# LEDMaster.net
KiCad netlist of a schematic drawn in EAGLE
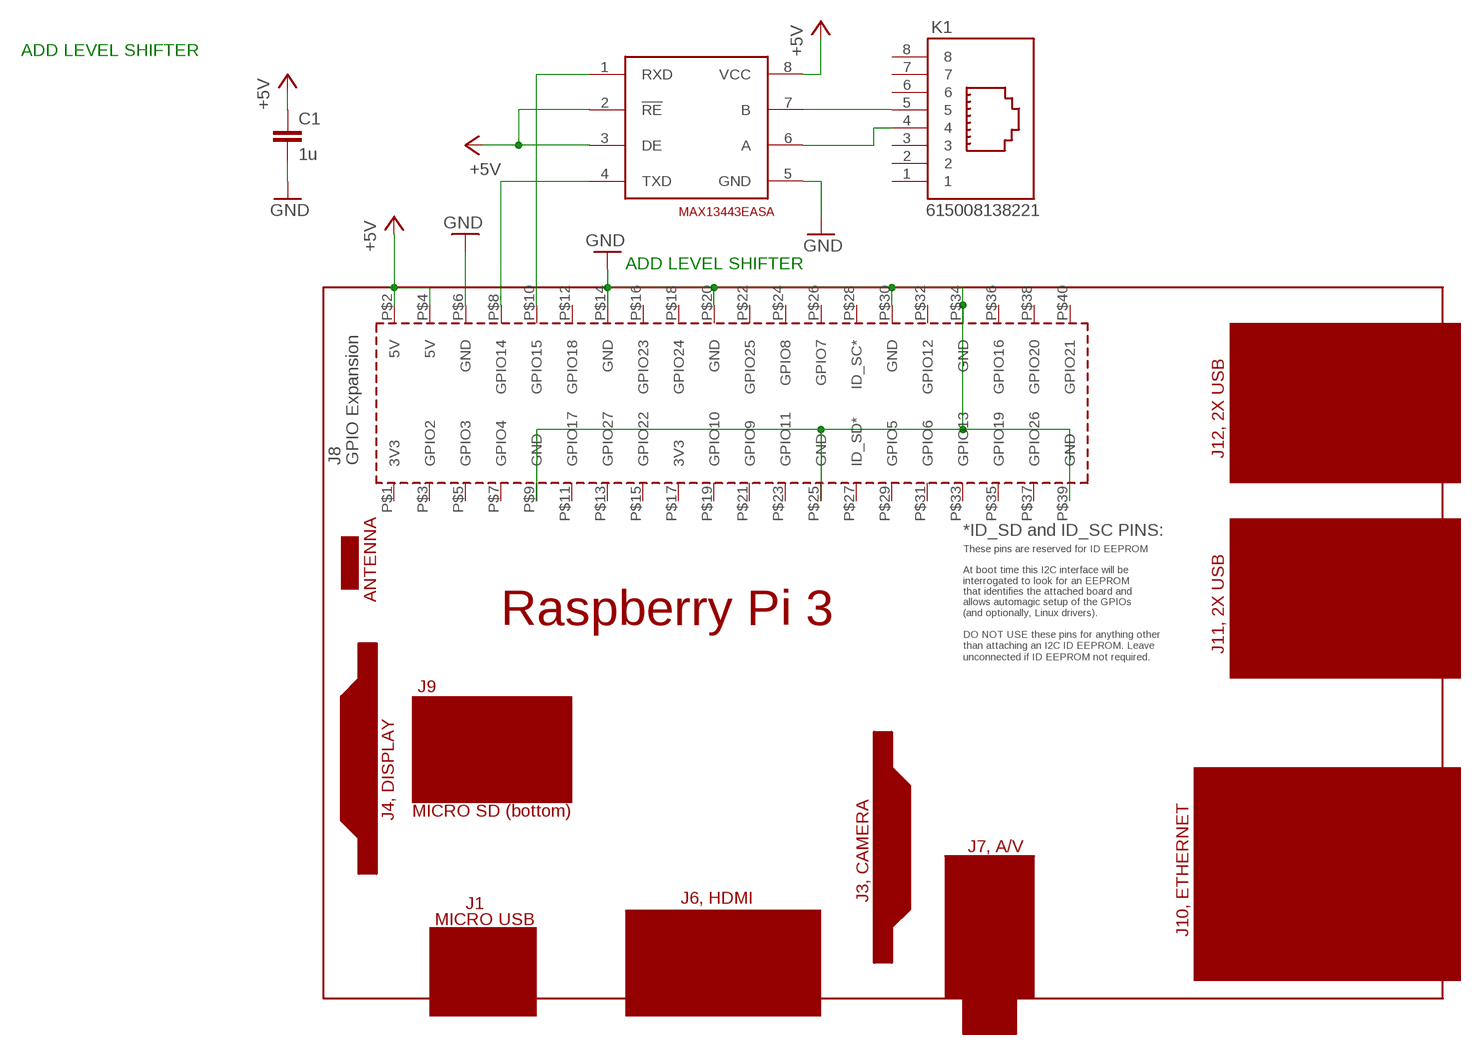
[diagram p0: schematic, sheet 1]

(export (version "E")
  (design (tool "Eeschema 10.0.6"))
  (components
    (comp (ref "C1")
      (value "1u")
      (footprint "eagle-import:C1206")
      (libsource (lib "eagle-import") (part "C-EUC1206"))
    )
    (comp (ref "K1")
      (value "615008138221")
      (footprint "eagle-import:615008138221")
      (libsource (lib "eagle-import") (part "615008138221"))
    )
    (comp (ref "PCB1")
      (value "RPI3")
      (footprint "eagle-import:RPI3")
      (libsource (lib "eagle-import") (part "RPI3"))
    )
    (comp (ref "U$1")
      (value "MAX13443EASA")
      (footprint "eagle-import:SO08")
      (libsource (lib "eagle-import") (part "MAX13443EASA"))
    )
  )
  (nets
    (net (code "1") (name "+5V") (class "Default")
      (node (ref "C1") (pin "1") (pinfunction "1_1") (pintype "passive"))
      (node (ref "PCB1") (pin "P$2") (pinfunction "5V_P$2") (pintype "bidirectional"))
      (node (ref "PCB1") (pin "P$4") (pinfunction "5V_P$4") (pintype "bidirectional"))
      (node (ref "U$1") (pin "2") (pinfunction "~{RE}_2") (pintype "bidirectional"))
      (node (ref "U$1") (pin "3") (pinfunction "DE_3") (pintype "bidirectional"))
      (node (ref "U$1") (pin "8") (pinfunction "VCC_8") (pintype "bidirectional"))
    )
    (net (code "2") (name "GND") (class "Default")
      (node (ref "C1") (pin "2") (pinfunction "2_2") (pintype "passive"))
      (node (ref "PCB1") (pin "P$14") (pinfunction "GND_P$14") (pintype "bidirectional"))
      (node (ref "PCB1") (pin "P$20") (pinfunction "GND_P$20") (pintype "bidirectional"))
      (node (ref "PCB1") (pin "P$25") (pinfunction "GND_P$25") (pintype "bidirectional"))
      (node (ref "PCB1") (pin "P$30") (pinfunction "GND_P$30") (pintype "bidirectional"))
      (node (ref "PCB1") (pin "P$34") (pinfunction "GND_P$34") (pintype "bidirectional"))
      (node (ref "PCB1") (pin "P$39") (pinfunction "GND_P$39") (pintype "bidirectional"))
      (node (ref "PCB1") (pin "P$6") (pinfunction "GND_P$6") (pintype "bidirectional"))
      (node (ref "PCB1") (pin "P$9") (pinfunction "GND_P$9") (pintype "bidirectional"))
      (node (ref "U$1") (pin "5") (pinfunction "GND_5") (pintype "bidirectional"))
    )
    (net (code "3") (name "Net-(PCB1-GPIO14)") (class "Default")
      (node (ref "PCB1") (pin "P$8") (pinfunction "GPIO14_P$8") (pintype "bidirectional"))
      (node (ref "U$1") (pin "4") (pinfunction "TXD_4") (pintype "bidirectional"))
    )
    (net (code "4") (name "Net-(PCB1-GPIO15)") (class "Default")
      (node (ref "PCB1") (pin "P$10") (pinfunction "GPIO15_P$10") (pintype "bidirectional"))
      (node (ref "U$1") (pin "1") (pinfunction "RXD_1") (pintype "bidirectional"))
    )
    (net (code "5") (name "Net-(U$1-A)") (class "Default")
      (node (ref "K1") (pin "4") (pinfunction "4_4") (pintype "passive"))
      (node (ref "U$1") (pin "6") (pinfunction "A_6") (pintype "bidirectional"))
    )
    (net (code "6") (name "Net-(U$1-B)") (class "Default")
      (node (ref "K1") (pin "5") (pinfunction "5_5") (pintype "passive"))
      (node (ref "U$1") (pin "7") (pinfunction "B_7") (pintype "bidirectional"))
    )
    (net (code "7") (name "unconnected-(K1-Pad1)") (class "Default")
      (node (ref "K1") (pin "1") (pinfunction "1_1") (pintype "passive"))
    )
    (net (code "8") (name "unconnected-(K1-Pad2)") (class "Default")
      (node (ref "K1") (pin "2") (pinfunction "2_2") (pintype "passive"))
    )
    (net (code "9") (name "unconnected-(K1-Pad3)") (class "Default")
      (node (ref "K1") (pin "3") (pinfunction "3_3") (pintype "passive"))
    )
    (net (code "10") (name "unconnected-(K1-Pad6)") (class "Default")
      (node (ref "K1") (pin "6") (pinfunction "6_6") (pintype "passive"))
    )
    (net (code "11") (name "unconnected-(K1-Pad7)") (class "Default")
      (node (ref "K1") (pin "7") (pinfunction "7_7") (pintype "passive"))
    )
    (net (code "12") (name "unconnected-(K1-Pad8)") (class "Default")
      (node (ref "K1") (pin "8") (pinfunction "8_8") (pintype "passive"))
    )
    (net (code "13") (name "unconnected-(PCB1-3V3-PadP$1)") (class "Default")
      (node (ref "PCB1") (pin "P$1") (pinfunction "3V3_P$1") (pintype "bidirectional"))
    )
    (net (code "14") (name "unconnected-(PCB1-3V3-PadP$17)") (class "Default")
      (node (ref "PCB1") (pin "P$17") (pinfunction "3V3_P$17") (pintype "bidirectional"))
    )
    (net (code "15") (name "unconnected-(PCB1-GPIO2-PadP$3)") (class "Default")
      (node (ref "PCB1") (pin "P$3") (pinfunction "GPIO2_P$3") (pintype "bidirectional"))
    )
    (net (code "16") (name "unconnected-(PCB1-GPIO3-PadP$5)") (class "Default")
      (node (ref "PCB1") (pin "P$5") (pinfunction "GPIO3_P$5") (pintype "bidirectional"))
    )
    (net (code "17") (name "unconnected-(PCB1-GPIO4-PadP$7)") (class "Default")
      (node (ref "PCB1") (pin "P$7") (pinfunction "GPIO4_P$7") (pintype "bidirectional"))
    )
    (net (code "18") (name "unconnected-(PCB1-GPIO5-PadP$29)") (class "Default")
      (node (ref "PCB1") (pin "P$29") (pinfunction "GPIO5_P$29") (pintype "bidirectional"))
    )
    (net (code "19") (name "unconnected-(PCB1-GPIO6-PadP$31)") (class "Default")
      (node (ref "PCB1") (pin "P$31") (pinfunction "GPIO6_P$31") (pintype "bidirectional"))
    )
    (net (code "20") (name "unconnected-(PCB1-GPIO7-PadP$26)") (class "Default")
      (node (ref "PCB1") (pin "P$26") (pinfunction "GPIO7_P$26") (pintype "bidirectional"))
    )
    (net (code "21") (name "unconnected-(PCB1-GPIO8-PadP$24)") (class "Default")
      (node (ref "PCB1") (pin "P$24") (pinfunction "GPIO8_P$24") (pintype "bidirectional"))
    )
    (net (code "22") (name "unconnected-(PCB1-GPIO9-PadP$21)") (class "Default")
      (node (ref "PCB1") (pin "P$21") (pinfunction "GPIO9_P$21") (pintype "bidirectional"))
    )
    (net (code "23") (name "unconnected-(PCB1-GPIO10-PadP$19)") (class "Default")
      (node (ref "PCB1") (pin "P$19") (pinfunction "GPIO10_P$19") (pintype "bidirectional"))
    )
    (net (code "24") (name "unconnected-(PCB1-GPIO11-PadP$23)") (class "Default")
      (node (ref "PCB1") (pin "P$23") (pinfunction "GPIO11_P$23") (pintype "bidirectional"))
    )
    (net (code "25") (name "unconnected-(PCB1-GPIO12-PadP$32)") (class "Default")
      (node (ref "PCB1") (pin "P$32") (pinfunction "GPIO12_P$32") (pintype "bidirectional"))
    )
    (net (code "26") (name "unconnected-(PCB1-GPIO13-PadP$33)") (class "Default")
      (node (ref "PCB1") (pin "P$33") (pinfunction "GPIO13_P$33") (pintype "bidirectional"))
    )
    (net (code "27") (name "unconnected-(PCB1-GPIO16-PadP$36)") (class "Default")
      (node (ref "PCB1") (pin "P$36") (pinfunction "GPIO16_P$36") (pintype "bidirectional"))
    )
    (net (code "28") (name "unconnected-(PCB1-GPIO17-PadP$11)") (class "Default")
      (node (ref "PCB1") (pin "P$11") (pinfunction "GPIO17_P$11") (pintype "bidirectional"))
    )
    (net (code "29") (name "unconnected-(PCB1-GPIO18-PadP$12)") (class "Default")
      (node (ref "PCB1") (pin "P$12") (pinfunction "GPIO18_P$12") (pintype "bidirectional"))
    )
    (net (code "30") (name "unconnected-(PCB1-GPIO19-PadP$35)") (class "Default")
      (node (ref "PCB1") (pin "P$35") (pinfunction "GPIO19_P$35") (pintype "bidirectional"))
    )
    (net (code "31") (name "unconnected-(PCB1-GPIO20-PadP$38)") (class "Default")
      (node (ref "PCB1") (pin "P$38") (pinfunction "GPIO20_P$38") (pintype "bidirectional"))
    )
    (net (code "32") (name "unconnected-(PCB1-GPIO21-PadP$40)") (class "Default")
      (node (ref "PCB1") (pin "P$40") (pinfunction "GPIO21_P$40") (pintype "bidirectional"))
    )
    (net (code "33") (name "unconnected-(PCB1-GPIO22-PadP$15)") (class "Default")
      (node (ref "PCB1") (pin "P$15") (pinfunction "GPIO22_P$15") (pintype "bidirectional"))
    )
    (net (code "34") (name "unconnected-(PCB1-GPIO23-PadP$16)") (class "Default")
      (node (ref "PCB1") (pin "P$16") (pinfunction "GPIO23_P$16") (pintype "bidirectional"))
    )
    (net (code "35") (name "unconnected-(PCB1-GPIO24-PadP$18)") (class "Default")
      (node (ref "PCB1") (pin "P$18") (pinfunction "GPIO24_P$18") (pintype "bidirectional"))
    )
    (net (code "36") (name "unconnected-(PCB1-GPIO25-PadP$22)") (class "Default")
      (node (ref "PCB1") (pin "P$22") (pinfunction "GPIO25_P$22") (pintype "bidirectional"))
    )
    (net (code "37") (name "unconnected-(PCB1-GPIO26-PadP$37)") (class "Default")
      (node (ref "PCB1") (pin "P$37") (pinfunction "GPIO26_P$37") (pintype "bidirectional"))
    )
    (net (code "38") (name "unconnected-(PCB1-GPIO27-PadP$13)") (class "Default")
      (node (ref "PCB1") (pin "P$13") (pinfunction "GPIO27_P$13") (pintype "bidirectional"))
    )
    (net (code "39") (name "unconnected-(PCB1-ID_SC*-PadP$28)") (class "Default")
      (node (ref "PCB1") (pin "P$28") (pinfunction "ID_SC*_P$28") (pintype "bidirectional"))
    )
    (net (code "40") (name "unconnected-(PCB1-ID_SD*-PadP$27)") (class "Default")
      (node (ref "PCB1") (pin "P$27") (pinfunction "ID_SD*_P$27") (pintype "bidirectional"))
    )
  )
)
